# smd.net
KiCad netlist of a schematic drawn in EAGLE
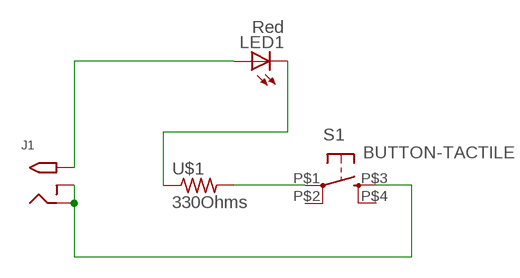
[diagram p0: schematic, sheet 1]

(export (version "E")
  (design (tool "Eeschema 10.0.6"))
  (components
    (comp (ref "J1")
      (value "2.1MMJACKTHM")
      (footprint "eagle-import:PJ-102A")
      (libsource (lib "eagle-import") (part "2.1MMJACKTHM"))
    )
    (comp (ref "LED1")
      (value "Red")
      (footprint "eagle-import:LED5MM")
      (libsource (lib "eagle-import") (part "LED5MM"))
    )
    (comp (ref "S1")
      (value "BUTTON-TACTILE")
      (footprint "eagle-import:LSH")
      (libsource (lib "eagle-import") (part "BUTTON-TACTILE"))
    )
    (comp (ref "U$1")
      (value "330Ohms")
      (footprint "eagle-import:RESAD1160W55L680D260_HS")
      (libsource (lib "eagle-import") (part "RESISTORTH-1/4W-CARBON"))
    )
  )
  (nets
    (net (code "1") (name "Net-(J1-PadTIP)") (class "Default")
      (node (ref "J1") (pin "TIP") (pinfunction "TIP_TIP") (pintype "bidirectional"))
      (node (ref "LED1") (pin "A") (pinfunction "A_A") (pintype "passive"))
    )
    (net (code "2") (name "Net-(LED1-C)") (class "Default")
      (node (ref "LED1") (pin "K") (pinfunction "C_K") (pintype "passive"))
      (node (ref "U$1") (pin "1") (pinfunction "1_1") (pintype "passive"))
    )
    (net (code "3") (name "Net-(S1-P)") (class "Default")
      (node (ref "S1") (pin "P$1") (pinfunction "P_P$1") (pintype "passive"))
      (node (ref "U$1") (pin "2") (pinfunction "2_2") (pintype "passive"))
    )
    (net (code "4") (name "Net-(S1-S)") (class "Default")
      (node (ref "J1") (pin "RING") (pinfunction "RING_RING") (pintype "bidirectional"))
      (node (ref "J1") (pin "RING_SW") (pinfunction "RING_SW_RING_SW") (pintype "bidirectional"))
      (node (ref "S1") (pin "P$3") (pinfunction "S_P$3") (pintype "passive"))
    )
    (net (code "5") (name "unconnected-(S1-P1-PadP$2)") (class "Default")
      (node (ref "S1") (pin "P$2") (pinfunction "P1_P$2") (pintype "passive"))
    )
    (net (code "6") (name "unconnected-(S1-S1-PadP$4)") (class "Default")
      (node (ref "S1") (pin "P$4") (pinfunction "S1_P$4") (pintype "passive"))
    )
  )
)
